# Goldilocks.net
KiCad netlist of a schematic drawn in EAGLE
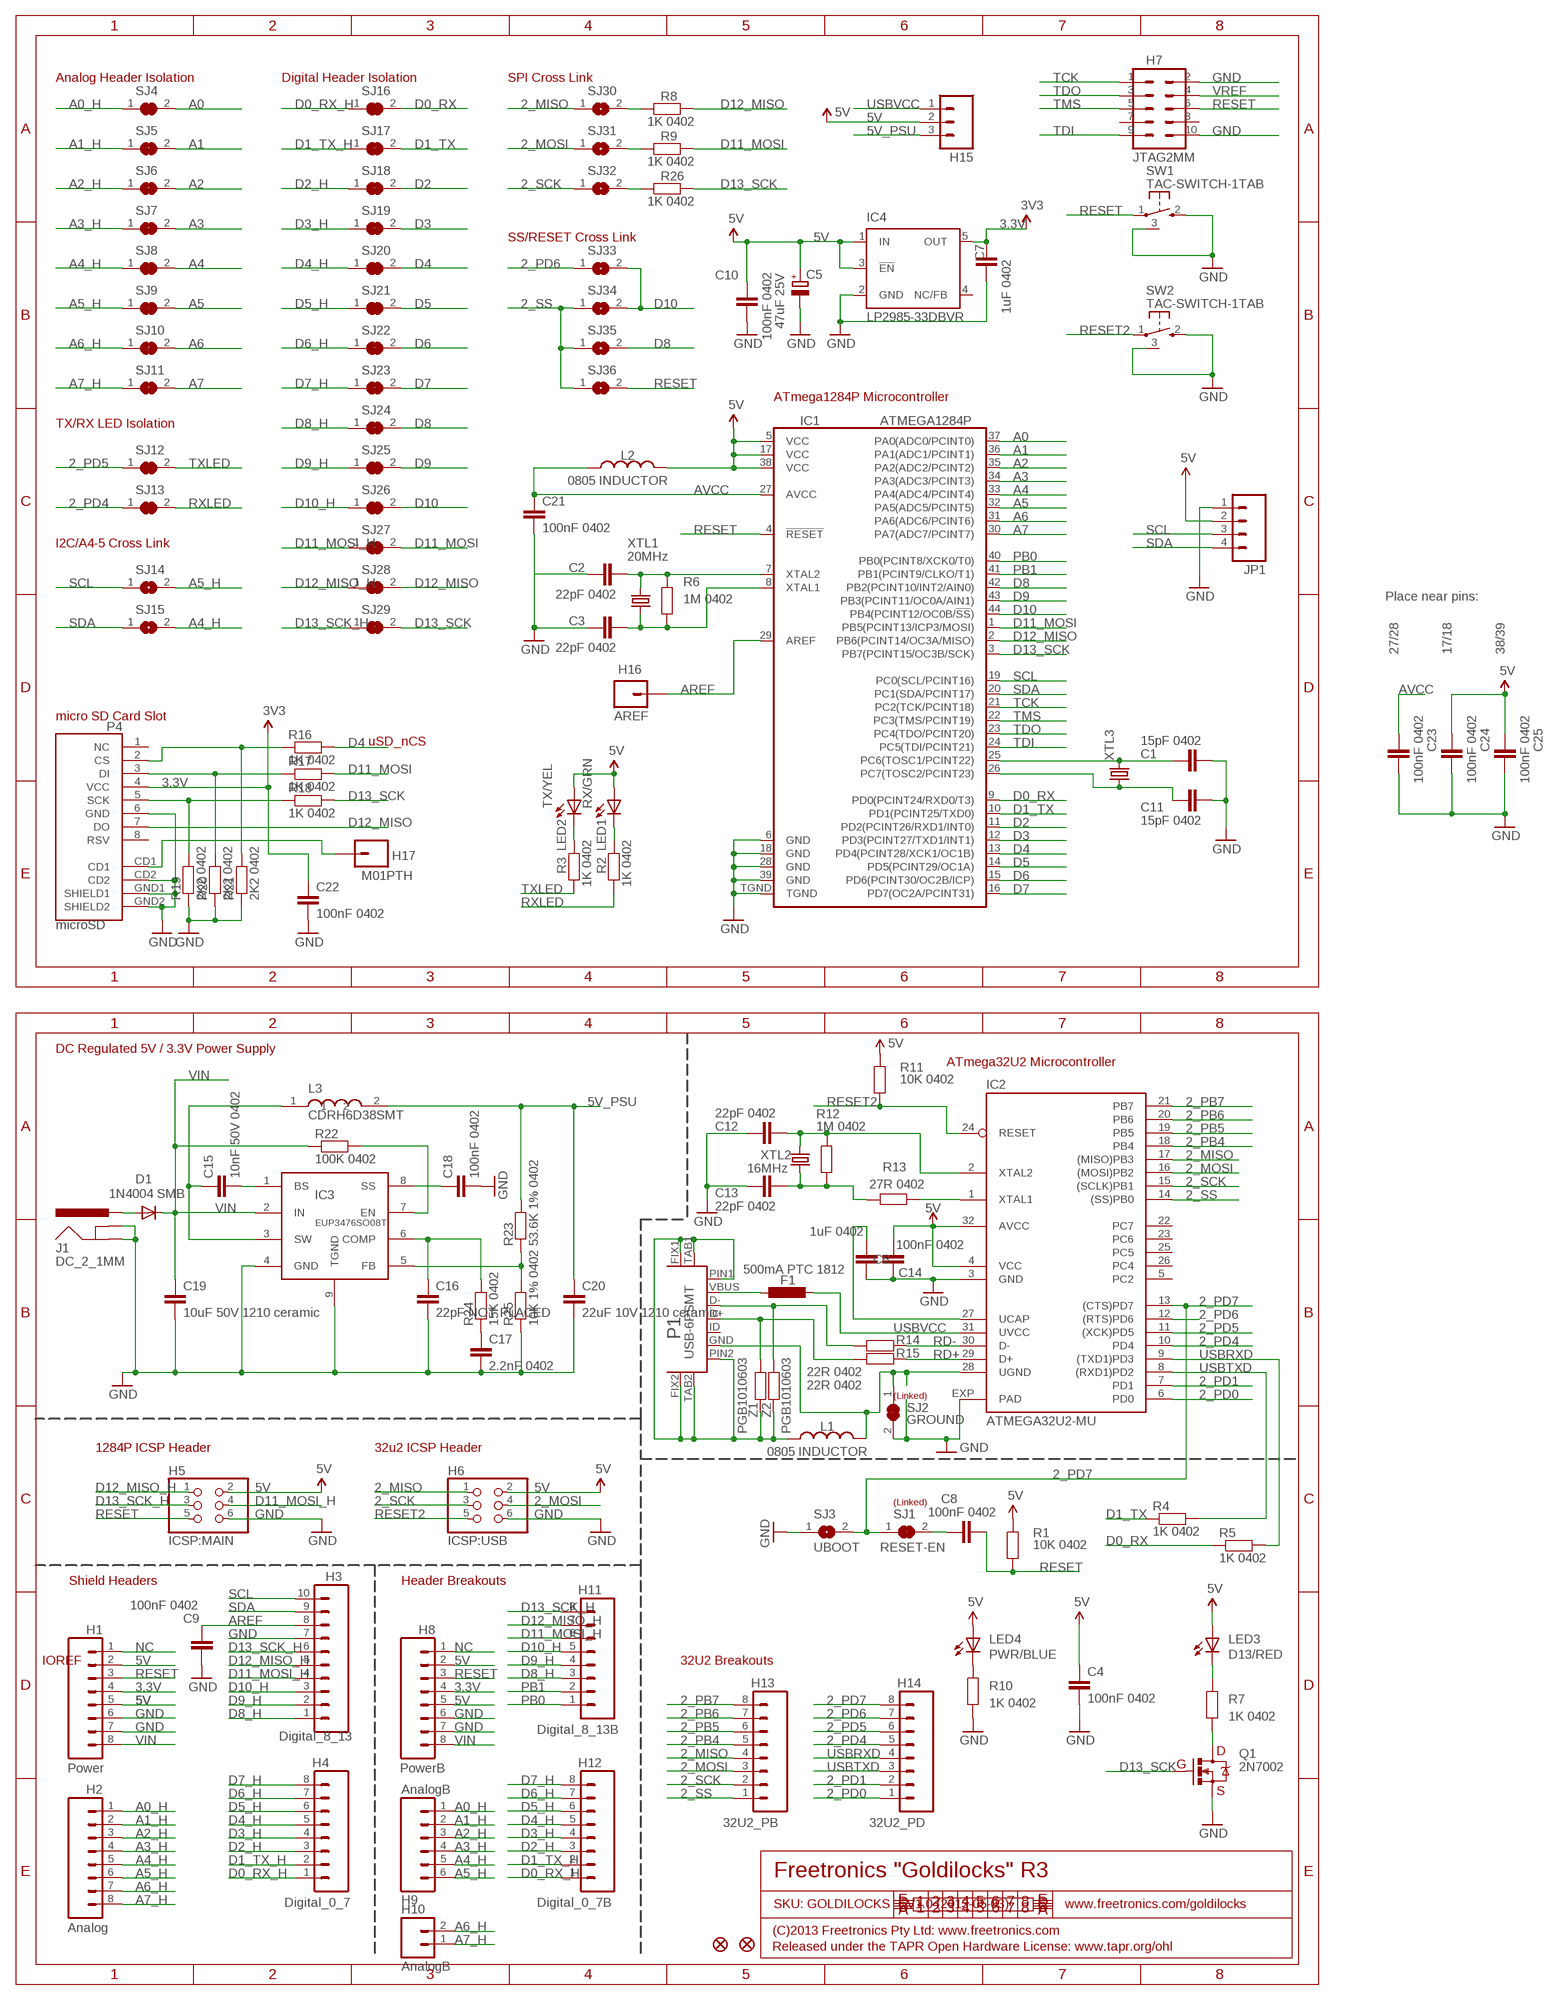
[diagram p0: schematic, sheet 1]

(export (version "E")
  (design (tool "Eeschema 10.0.6"))
  (components
    (comp (ref "C1")
      (value "15pF 0402")
      (footprint "eagle-import:0402C")
      (libsource (lib "eagle-import") (part "C-EU0402C"))
    )
    (comp (ref "C2")
      (value "22pF 0402")
      (footprint "eagle-import:0402C")
      (libsource (lib "eagle-import") (part "C-EU0402C"))
    )
    (comp (ref "C3")
      (value "22pF 0402")
      (footprint "eagle-import:0402C")
      (libsource (lib "eagle-import") (part "C-EU0402C"))
    )
    (comp (ref "C4")
      (value "100nF 0402")
      (footprint "eagle-import:0402C")
      (libsource (lib "eagle-import") (part "C-EU0402C"))
    )
    (comp (ref "C5")
      (value "47uF 25V")
      (footprint "eagle-import:PANASONIC_D")
      (libsource (lib "eagle-import") (part "CPOL-EUD"))
    )
    (comp (ref "C6")
      (value "1uF 0402")
      (footprint "eagle-import:0402C")
      (libsource (lib "eagle-import") (part "C-EU0402C"))
    )
    (comp (ref "C7")
      (value "1uF 0402")
      (footprint "eagle-import:0402C")
      (libsource (lib "eagle-import") (part "C-EU0402C"))
    )
    (comp (ref "C8")
      (value "100nF 0402")
      (footprint "eagle-import:0402C")
      (libsource (lib "eagle-import") (part "C-EU0402C"))
    )
    (comp (ref "C9")
      (value "100nF 0402")
      (footprint "eagle-import:0402C")
      (libsource (lib "eagle-import") (part "C-EU0402C"))
    )
    (comp (ref "C10")
      (value "100nF 0402")
      (footprint "eagle-import:0402C")
      (libsource (lib "eagle-import") (part "C-EU0402C"))
    )
    (comp (ref "C11")
      (value "15pF 0402")
      (footprint "eagle-import:0402C")
      (libsource (lib "eagle-import") (part "C-EU0402C"))
    )
    (comp (ref "C12")
      (value "22pF 0402")
      (footprint "eagle-import:0402C")
      (libsource (lib "eagle-import") (part "C-EU0402C"))
    )
    (comp (ref "C13")
      (value "22pF 0402")
      (footprint "eagle-import:0402C")
      (libsource (lib "eagle-import") (part "C-EU0402C"))
    )
    (comp (ref "C14")
      (value "100nF 0402")
      (footprint "eagle-import:0402C")
      (libsource (lib "eagle-import") (part "C-EU0402C"))
    )
    (comp (ref "C15")
      (value "10nF 50V 0402")
      (footprint "eagle-import:0402C")
      (libsource (lib "eagle-import") (part "C-EU0402C"))
    )
    (comp (ref "C16")
      (value "22pF NOT PLACED")
      (footprint "eagle-import:0402C")
      (libsource (lib "eagle-import") (part "C-EU0402C"))
    )
    (comp (ref "C17")
      (value "2.2nF 0402")
      (footprint "eagle-import:0402C")
      (libsource (lib "eagle-import") (part "C-EU0402C"))
    )
    (comp (ref "C18")
      (value "100nF 0402")
      (footprint "eagle-import:0402C")
      (libsource (lib "eagle-import") (part "C-EU0402C"))
    )
    (comp (ref "C19")
      (value "10uF 50V 1210 ceramic")
      (footprint "eagle-import:C1210")
      (libsource (lib "eagle-import") (part "C-EUC1210"))
    )
    (comp (ref "C20")
      (value "22uF 10V 1210 ceramic")
      (footprint "eagle-import:C1210")
      (libsource (lib "eagle-import") (part "C-EUC1210"))
    )
    (comp (ref "C21")
      (value "100nF 0402")
      (footprint "eagle-import:0402C")
      (libsource (lib "eagle-import") (part "C-EU0402C"))
    )
    (comp (ref "C22")
      (value "100nF 0402")
      (footprint "eagle-import:0402C")
      (libsource (lib "eagle-import") (part "C-EU0402C"))
    )
    (comp (ref "C23")
      (value "100nF 0402")
      (footprint "eagle-import:0402C")
      (libsource (lib "eagle-import") (part "C-EU0402C"))
    )
    (comp (ref "C24")
      (value "100nF 0402")
      (footprint "eagle-import:0402C")
      (libsource (lib "eagle-import") (part "C-EU0402C"))
    )
    (comp (ref "C25")
      (value "100nF 0402")
      (footprint "eagle-import:0402C")
      (libsource (lib "eagle-import") (part "C-EU0402C"))
    )
    (comp (ref "D1")
      (value "1N4004 SMB")
      (footprint "eagle-import:SMB-DIODE")
      (libsource (lib "eagle-import") (part "DIODESMB"))
    )
    (comp (ref "F1")
      (value "500mA PTC 1812")
      (footprint "eagle-import:L1812")
      (libsource (lib "eagle-import") (part "L-EUL1812"))
    )
    (comp (ref "H1")
      (value "Power")
      (footprint "eagle-import:1X08")
      (libsource (lib "eagle-import") (part "M08"))
    )
    (comp (ref "H2")
      (value "Analog")
      (footprint "eagle-import:1X08")
      (libsource (lib "eagle-import") (part "M08"))
    )
    (comp (ref "H3")
      (value "Digital_8_13")
      (footprint "eagle-import:1X10")
      (libsource (lib "eagle-import") (part "M100.1"))
    )
    (comp (ref "H4")
      (value "Digital_0_7")
      (footprint "eagle-import:1X08")
      (libsource (lib "eagle-import") (part "M08"))
    )
    (comp (ref "H5")
      (value "ICSP:MAIN")
      (footprint "eagle-import:2X03")
      (libsource (lib "eagle-import") (part "PINHD-2X3"))
    )
    (comp (ref "H6")
      (value "ICSP:USB")
      (footprint "eagle-import:2X03")
      (libsource (lib "eagle-import") (part "PINHD-2X3"))
    )
    (comp (ref "H7")
      (value "JTAG2MM")
      (footprint "eagle-import:SAMTEC-TMM-DOUBLE")
      (libsource (lib "eagle-import") (part "JTAG2MM"))
    )
    (comp (ref "H8")
      (value "PowerB")
      (footprint "eagle-import:1X08")
      (libsource (lib "eagle-import") (part "M08"))
    )
    (comp (ref "H9")
      (value "AnalogB")
      (footprint "eagle-import:1X06")
      (libsource (lib "eagle-import") (part "M06SIP"))
    )
    (comp (ref "H10")
      (value "AnalogB")
      (footprint "eagle-import:1X02")
      (libsource (lib "eagle-import") (part "M02PTH"))
    )
    (comp (ref "H11")
      (value "Digital_8_13B")
      (footprint "eagle-import:1X08")
      (libsource (lib "eagle-import") (part "M08"))
    )
    (comp (ref "H12")
      (value "Digital_0_7B")
      (footprint "eagle-import:1X08")
      (libsource (lib "eagle-import") (part "M08"))
    )
    (comp (ref "H13")
      (value "32U2_PB")
      (footprint "eagle-import:1X08")
      (libsource (lib "eagle-import") (part "M08"))
    )
    (comp (ref "H14")
      (value "32U2_PD")
      (footprint "eagle-import:1X08")
      (libsource (lib "eagle-import") (part "M08"))
    )
    (comp (ref "H15")
      (value "M03PTH")
      (footprint "eagle-import:1X03")
      (libsource (lib "eagle-import") (part "M03PTH"))
    )
    (comp (ref "H16")
      (value "AREF")
      (footprint "eagle-import:1X01")
      (libsource (lib "eagle-import") (part "M01PTH"))
    )
    (comp (ref "H17")
      (value "M01PTH")
      (footprint "eagle-import:1X01")
      (libsource (lib "eagle-import") (part "M01PTH"))
    )
    (comp (ref "IC1")
      (value "ATMEGA1284P")
      (footprint "eagle-import:QFN-44M1")
      (libsource (lib "eagle-import") (part "ATMEGA1284P"))
    )
    (comp (ref "IC2")
      (value "ATMEGA32U2-MU")
      (footprint "eagle-import:ATMEL_QFN32")
      (libsource (lib "eagle-import") (part "ATMEL_ATMEGA8U2-MUQFN"))
    )
    (comp (ref "IC3")
      (value "EUP3476SO08T")
      (footprint "eagle-import:SO08T")
      (libsource (lib "eagle-import") (part "EUP3476SO08T"))
    )
    (comp (ref "IC4")
      (value "LP2985-33DBVR")
      (footprint "eagle-import:TEXAS_SOT23-DBV")
      (libsource (lib "eagle-import") (part "TEXAS_TPS77033"))
    )
    (comp (ref "J1")
      (value "DC_2_1MM")
      (footprint "eagle-import:POWER_JACK_PTH")
      (libsource (lib "eagle-import") (part "POWER_JACKPTH"))
    )
    (comp (ref "JP1")
      (value "M04PTH")
      (footprint "eagle-import:1X04")
      (libsource (lib "eagle-import") (part "M04PTH"))
    )
    (comp (ref "L1")
      (value "0805 INDUCTOR")
      (footprint "eagle-import:0805-LARGE")
      (libsource (lib "eagle-import") (part "INDUCTOR0805-LARGE"))
    )
    (comp (ref "L2")
      (value "0805 INDUCTOR")
      (footprint "eagle-import:0805-LARGE")
      (libsource (lib "eagle-import") (part "INDUCTOR0805-LARGE"))
    )
    (comp (ref "L3")
      (value "CDRH6D38SMT")
      (footprint "eagle-import:CDRH")
      (libsource (lib "eagle-import") (part "CDRH6D38SMT"))
    )
    (comp (ref "LED1")
      (value "RX/GRN")
      (footprint "eagle-import:LED-0402")
      (libsource (lib "eagle-import") (part "LED0402"))
    )
    (comp (ref "LED2")
      (value "TX/YEL")
      (footprint "eagle-import:LED-0402")
      (libsource (lib "eagle-import") (part "LED0402"))
    )
    (comp (ref "LED3")
      (value "D13/RED")
      (footprint "eagle-import:LED-0402")
      (libsource (lib "eagle-import") (part "LED0402"))
    )
    (comp (ref "LED4")
      (value "PWR/BLUE")
      (footprint "eagle-import:LED-0402")
      (libsource (lib "eagle-import") (part "LED0402"))
    )
    (comp (ref "P1")
      (value "USB-6PSMT")
      (footprint "eagle-import:USB-MICROB-MB05PMXX")
      (libsource (lib "eagle-import") (part "USB-6PSMT"))
    )
    (comp (ref "P4")
      (value "microSD")
      (footprint "eagle-import:MICRO-SD-SOCKET-PP")
      (libsource (lib "eagle-import") (part "USD-SOCKETNEW"))
    )
    (comp (ref "Q1")
      (value "2N7002")
      (footprint "eagle-import:SOT23-3")
      (libsource (lib "eagle-import") (part "MOSFET-NCHANNELSMD"))
    )
    (comp (ref "R1")
      (value "10K 0402")
      (footprint "eagle-import:0402")
      (libsource (lib "eagle-import") (part "freetronics-jon_RESISTOR0402"))
    )
    (comp (ref "R2")
      (value "1K 0402")
      (footprint "eagle-import:0402")
      (libsource (lib "eagle-import") (part "freetronics-jon_RESISTOR0402"))
    )
    (comp (ref "R3")
      (value "1K 0402")
      (footprint "eagle-import:0402")
      (libsource (lib "eagle-import") (part "freetronics-jon_RESISTOR0402"))
    )
    (comp (ref "R4")
      (value "1K 0402")
      (footprint "eagle-import:0402")
      (libsource (lib "eagle-import") (part "freetronics-jon_RESISTOR0402"))
    )
    (comp (ref "R5")
      (value "1K 0402")
      (footprint "eagle-import:0402")
      (libsource (lib "eagle-import") (part "freetronics-jon_RESISTOR0402"))
    )
    (comp (ref "R6")
      (value "1M 0402")
      (footprint "eagle-import:0402")
      (libsource (lib "eagle-import") (part "freetronics-jon_RESISTOR0402"))
    )
    (comp (ref "R7")
      (value "1K 0402")
      (footprint "eagle-import:0402")
      (libsource (lib "eagle-import") (part "freetronics-jon_RESISTOR0402"))
    )
    (comp (ref "R8")
      (value "1K 0402")
      (footprint "eagle-import:0402")
      (libsource (lib "eagle-import") (part "freetronics-jon_RESISTOR0402"))
    )
    (comp (ref "R9")
      (value "1K 0402")
      (footprint "eagle-import:0402")
      (libsource (lib "eagle-import") (part "freetronics-jon_RESISTOR0402"))
    )
    (comp (ref "R10")
      (value "1K 0402")
      (footprint "eagle-import:0402")
      (libsource (lib "eagle-import") (part "freetronics-jon_RESISTOR0402"))
    )
    (comp (ref "R11")
      (value "10K 0402")
      (footprint "eagle-import:0402")
      (libsource (lib "eagle-import") (part "freetronics-jon_RESISTOR0402"))
    )
    (comp (ref "R12")
      (value "1M 0402")
      (footprint "eagle-import:0402")
      (libsource (lib "eagle-import") (part "freetronics-jon_RESISTOR0402"))
    )
    (comp (ref "R13")
      (value "27R 0402")
      (footprint "eagle-import:0402")
      (libsource (lib "eagle-import") (part "freetronics-jon_RESISTOR0402"))
    )
    (comp (ref "R14")
      (value "22R 0402")
      (footprint "eagle-import:0402")
      (libsource (lib "eagle-import") (part "freetronics-jon_RESISTOR0402"))
    )
    (comp (ref "R15")
      (value "22R 0402")
      (footprint "eagle-import:0402")
      (libsource (lib "eagle-import") (part "freetronics-jon_RESISTOR0402"))
    )
    (comp (ref "R16")
      (value "1K 0402")
      (footprint "eagle-import:0402")
      (libsource (lib "eagle-import") (part "freetronics-jon_RESISTOR0402"))
    )
    (comp (ref "R17")
      (value "1K 0402")
      (footprint "eagle-import:0402")
      (libsource (lib "eagle-import") (part "freetronics-jon_RESISTOR0402"))
    )
    (comp (ref "R18")
      (value "1K 0402")
      (footprint "eagle-import:0402")
      (libsource (lib "eagle-import") (part "freetronics-jon_RESISTOR0402"))
    )
    (comp (ref "R19")
      (value "2K2 0402")
      (footprint "eagle-import:0402")
      (libsource (lib "eagle-import") (part "freetronics-jon_RESISTOR0402"))
    )
    (comp (ref "R20")
      (value "2K2 0402")
      (footprint "eagle-import:0402")
      (libsource (lib "eagle-import") (part "freetronics-jon_RESISTOR0402"))
    )
    (comp (ref "R21")
      (value "2K2 0402")
      (footprint "eagle-import:0402")
      (libsource (lib "eagle-import") (part "freetronics-jon_RESISTOR0402"))
    )
    (comp (ref "R22")
      (value "100K 0402")
      (footprint "eagle-import:0402")
      (libsource (lib "eagle-import") (part "freetronics-jon_RESISTOR0402"))
    )
    (comp (ref "R23")
      (value "53.6K 1% 0402")
      (footprint "eagle-import:0402")
      (libsource (lib "eagle-import") (part "freetronics-jon_RESISTOR0402"))
    )
    (comp (ref "R24")
      (value "15K 0402")
      (footprint "eagle-import:0402")
      (libsource (lib "eagle-import") (part "freetronics-jon_RESISTOR0402"))
    )
    (comp (ref "R25")
      (value "10K 1% 0402")
      (footprint "eagle-import:0402")
      (libsource (lib "eagle-import") (part "freetronics-jon_RESISTOR0402"))
    )
    (comp (ref "R26")
      (value "1K 0402")
      (footprint "eagle-import:0402")
      (libsource (lib "eagle-import") (part "freetronics-jon_RESISTOR0402"))
    )
    (comp (ref "SJ1")
      (value "RESET-EN")
      (footprint "eagle-import:SJC")
      (libsource (lib "eagle-import") (part "SJCN"))
    )
    (comp (ref "SJ2")
      (value "GROUND")
      (footprint "eagle-import:SJC")
      (libsource (lib "eagle-import") (part "SJCN"))
    )
    (comp (ref "SJ3")
      (value "UBOOT")
      (footprint "eagle-import:SJ")
      (libsource (lib "eagle-import") (part "jumper_SJ"))
    )
    (comp (ref "SJ4")
      (value "SJC0402")
      (footprint "eagle-import:0402SJC")
      (libsource (lib "eagle-import") (part "SJC0402"))
    )
    (comp (ref "SJ5")
      (value "SJC0402")
      (footprint "eagle-import:0402SJC")
      (libsource (lib "eagle-import") (part "SJC0402"))
    )
    (comp (ref "SJ6")
      (value "SJC0402")
      (footprint "eagle-import:0402SJC")
      (libsource (lib "eagle-import") (part "SJC0402"))
    )
    (comp (ref "SJ7")
      (value "SJC0402")
      (footprint "eagle-import:0402SJC")
      (libsource (lib "eagle-import") (part "SJC0402"))
    )
    (comp (ref "SJ8")
      (value "SJC0402")
      (footprint "eagle-import:0402SJC")
      (libsource (lib "eagle-import") (part "SJC0402"))
    )
    (comp (ref "SJ9")
      (value "SJC0402")
      (footprint "eagle-import:0402SJC")
      (libsource (lib "eagle-import") (part "SJC0402"))
    )
    (comp (ref "SJ10")
      (value "SJC0402")
      (footprint "eagle-import:0402SJC")
      (libsource (lib "eagle-import") (part "SJC0402"))
    )
    (comp (ref "SJ11")
      (value "SJC0402")
      (footprint "eagle-import:0402SJC")
      (libsource (lib "eagle-import") (part "SJC0402"))
    )
    (comp (ref "SJ12")
      (value "SJC0402")
      (footprint "eagle-import:0402SJC")
      (libsource (lib "eagle-import") (part "SJC0402"))
    )
    (comp (ref "SJ13")
      (value "SJC0402")
      (footprint "eagle-import:0402SJC")
      (libsource (lib "eagle-import") (part "SJC0402"))
    )
    (comp (ref "SJ14")
      (value "SJ")
      (footprint "eagle-import:SJ")
      (libsource (lib "eagle-import") (part "SJ"))
    )
    (comp (ref "SJ15")
      (value "SJ")
      (footprint "eagle-import:SJ")
      (libsource (lib "eagle-import") (part "SJ"))
    )
    (comp (ref "SJ16")
      (value "SJC0402")
      (footprint "eagle-import:0402SJC")
      (libsource (lib "eagle-import") (part "SJC0402"))
    )
    (comp (ref "SJ17")
      (value "SJC0402")
      (footprint "eagle-import:0402SJC")
      (libsource (lib "eagle-import") (part "SJC0402"))
    )
    (comp (ref "SJ18")
      (value "SJC0402")
      (footprint "eagle-import:0402SJC")
      (libsource (lib "eagle-import") (part "SJC0402"))
    )
    (comp (ref "SJ19")
      (value "SJC0402")
      (footprint "eagle-import:0402SJC")
      (libsource (lib "eagle-import") (part "SJC0402"))
    )
    (comp (ref "SJ20")
      (value "SJC0402")
      (footprint "eagle-import:0402SJC")
      (libsource (lib "eagle-import") (part "SJC0402"))
    )
    (comp (ref "SJ21")
      (value "SJC0402")
      (footprint "eagle-import:0402SJC")
      (libsource (lib "eagle-import") (part "SJC0402"))
    )
    (comp (ref "SJ22")
      (value "SJC0402")
      (footprint "eagle-import:0402SJC")
      (libsource (lib "eagle-import") (part "SJC0402"))
    )
    (comp (ref "SJ23")
      (value "SJC0402")
      (footprint "eagle-import:0402SJC")
      (libsource (lib "eagle-import") (part "SJC0402"))
    )
    (comp (ref "SJ24")
      (value "SJC0402")
      (footprint "eagle-import:0402SJC")
      (libsource (lib "eagle-import") (part "SJC0402"))
    )
    (comp (ref "SJ25")
      (value "SJC0402")
      (footprint "eagle-import:0402SJC")
      (libsource (lib "eagle-import") (part "SJC0402"))
    )
    (comp (ref "SJ26")
      (value "SJC0402")
      (footprint "eagle-import:0402SJC")
      (libsource (lib "eagle-import") (part "SJC0402"))
    )
    (comp (ref "SJ27")
      (value "SJC0402")
      (footprint "eagle-import:0402SJC")
      (libsource (lib "eagle-import") (part "SJC0402"))
    )
    (comp (ref "SJ28")
      (value "SJC0402")
      (footprint "eagle-import:0402SJC")
      (libsource (lib "eagle-import") (part "SJC0402"))
    )
    (comp (ref "SJ29")
      (value "SJC0402")
      (footprint "eagle-import:0402SJC")
      (libsource (lib "eagle-import") (part "SJC0402"))
    )
    (comp (ref "SJ30")
      (value "MISO")
      (footprint "eagle-import:SJ")
      (libsource (lib "eagle-import") (part "SJN"))
    )
    (comp (ref "SJ31")
      (value "MOSI")
      (footprint "eagle-import:SJ")
      (libsource (lib "eagle-import") (part "SJN"))
    )
    (comp (ref "SJ32")
      (value "SCK")
      (footprint "eagle-import:SJ")
      (libsource (lib "eagle-import") (part "SJN"))
    )
    (comp (ref "SJ33")
      (value "SJN")
      (footprint "eagle-import:SJ")
      (libsource (lib "eagle-import") (part "SJN"))
    )
    (comp (ref "SJ34")
      (value "SJN")
      (footprint "eagle-import:SJ")
      (libsource (lib "eagle-import") (part "SJN"))
    )
    (comp (ref "SJ35")
      (value "SJN")
      (footprint "eagle-import:SJ")
      (libsource (lib "eagle-import") (part "SJN"))
    )
    (comp (ref "SJ36")
      (value "SJN")
      (footprint "eagle-import:SJ")
      (libsource (lib "eagle-import") (part "SJN"))
    )
    (comp (ref "SW1")
      (value "TAC-SWITCH-1TAB")
      (footprint "eagle-import:TACT-VERT-1TAB")
      (libsource (lib "eagle-import") (part "TAC-SWITCH-1TAB"))
    )
    (comp (ref "SW2")
      (value "TAC-SWITCH-1TAB")
      (footprint "eagle-import:TACT-VERT-1TAB")
      (libsource (lib "eagle-import") (part "TAC-SWITCH-1TAB"))
    )
    (comp (ref "U$5")
      (value "FIDUCIAL1X2.5")
      (footprint "eagle-import:FIDUCIAL-1X2.5")
      (libsource (lib "eagle-import") (part "FIDUCIAL1X2.5"))
    )
    (comp (ref "U$14")
      (value "FIDUCIAL1X2.5")
      (footprint "eagle-import:FIDUCIAL-1X2.5")
      (libsource (lib "eagle-import") (part "FIDUCIAL1X2.5"))
    )
    (comp (ref "XTL1")
      (value "20MHz")
      (footprint "eagle-import:HC49U-V")
      (libsource (lib "eagle-import") (part "CRYSTALHC49UV"))
    )
    (comp (ref "XTL2")
      (value "16MHz")
      (footprint "eagle-import:HC49U-V")
      (libsource (lib "eagle-import") (part "CRYSTALHC49UV"))
    )
    (comp (ref "XTL3")
      (value "CRYSTALTC38H")
      (footprint "eagle-import:TC38H")
      (libsource (lib "eagle-import") (part "freetronics-original_CRYSTALTC38H"))
    )
    (comp (ref "Z1")
      (value "PGB1010603")
      (footprint "eagle-import:0603")
      (libsource (lib "eagle-import") (part "RESISTOR0603"))
    )
    (comp (ref "Z2")
      (value "PGB1010603")
      (footprint "eagle-import:0603")
      (libsource (lib "eagle-import") (part "RESISTOR0603"))
    )
  )
  (nets
    (net (code "1") (name "/2_MISO") (class "Default")
      (node (ref "H13") (pin "4") (pinfunction "4_4") (pintype "passive"))
      (node (ref "H6") (pin "1") (pinfunction "1_1") (pintype "passive"))
      (node (ref "IC2") (pin "17") (pinfunction "(MISO)PB3_17") (pintype "bidirectional"))
      (node (ref "SJ30") (pin "1") (pinfunction "1_1") (pintype "passive"))
    )
    (net (code "2") (name "/2_MOSI") (class "Default")
      (node (ref "H13") (pin "3") (pinfunction "3_3") (pintype "passive"))
      (node (ref "H6") (pin "4") (pinfunction "4_4") (pintype "passive"))
      (node (ref "IC2") (pin "16") (pinfunction "(MOSI)PB2_16") (pintype "bidirectional"))
      (node (ref "SJ31") (pin "1") (pinfunction "1_1") (pintype "passive"))
    )
    (net (code "3") (name "/2_PB4") (class "Default")
      (node (ref "H13") (pin "5") (pinfunction "5_5") (pintype "passive"))
      (node (ref "IC2") (pin "18") (pinfunction "PB4_18") (pintype "bidirectional"))
    )
    (net (code "4") (name "/2_PB5") (class "Default")
      (node (ref "H13") (pin "6") (pinfunction "6_6") (pintype "passive"))
      (node (ref "IC2") (pin "19") (pinfunction "PB5_19") (pintype "bidirectional"))
    )
    (net (code "5") (name "/2_PB6") (class "Default")
      (node (ref "H13") (pin "7") (pinfunction "7_7") (pintype "passive"))
      (node (ref "IC2") (pin "20") (pinfunction "PB6_20") (pintype "bidirectional"))
    )
    (net (code "6") (name "/2_PB7") (class "Default")
      (node (ref "H13") (pin "8") (pinfunction "8_8") (pintype "passive"))
      (node (ref "IC2") (pin "21") (pinfunction "PB7_21") (pintype "bidirectional"))
    )
    (net (code "7") (name "/2_PD0") (class "Default")
      (node (ref "H14") (pin "1") (pinfunction "1_1") (pintype "passive"))
      (node (ref "IC2") (pin "6") (pinfunction "PD0_6") (pintype "bidirectional"))
    )
    (net (code "8") (name "/2_PD1") (class "Default")
      (node (ref "H14") (pin "2") (pinfunction "2_2") (pintype "passive"))
      (node (ref "IC2") (pin "7") (pinfunction "PD1_7") (pintype "bidirectional"))
    )
    (net (code "9") (name "/2_PD4") (class "Default")
      (node (ref "H14") (pin "5") (pinfunction "5_5") (pintype "passive"))
      (node (ref "IC2") (pin "10") (pinfunction "PD4_10") (pintype "bidirectional"))
      (node (ref "SJ13") (pin "1") (pinfunction "1_1") (pintype "passive"))
    )
    (net (code "10") (name "/2_PD5") (class "Default")
      (node (ref "H14") (pin "6") (pinfunction "6_6") (pintype "passive"))
      (node (ref "IC2") (pin "11") (pinfunction "(XCK)PD5_11") (pintype "bidirectional"))
      (node (ref "SJ12") (pin "1") (pinfunction "1_1") (pintype "passive"))
    )
    (net (code "11") (name "/2_PD6") (class "Default")
      (node (ref "H14") (pin "7") (pinfunction "7_7") (pintype "passive"))
      (node (ref "IC2") (pin "12") (pinfunction "(RTS)PD6_12") (pintype "bidirectional"))
      (node (ref "SJ33") (pin "1") (pinfunction "1_1") (pintype "passive"))
    )
    (net (code "12") (name "/2_PD7") (class "Default")
      (node (ref "H14") (pin "8") (pinfunction "8_8") (pintype "passive"))
      (node (ref "IC2") (pin "13") (pinfunction "(CTS)PD7_13") (pintype "bidirectional"))
      (node (ref "SJ1") (pin "1") (pinfunction "1_1") (pintype "passive"))
      (node (ref "SJ3") (pin "2") (pinfunction "2_2") (pintype "passive"))
    )
    (net (code "13") (name "/2_SCK") (class "Default")
      (node (ref "H13") (pin "2") (pinfunction "2_2") (pintype "passive"))
      (node (ref "H6") (pin "3") (pinfunction "3_3") (pintype "passive"))
      (node (ref "IC2") (pin "15") (pinfunction "(SCLK)PB1_15") (pintype "bidirectional"))
      (node (ref "SJ32") (pin "1") (pinfunction "1_1") (pintype "passive"))
    )
    (net (code "14") (name "/2_SS") (class "Default")
      (node (ref "H13") (pin "1") (pinfunction "1_1") (pintype "passive"))
      (node (ref "IC2") (pin "14") (pinfunction "(SS)PB0_14") (pintype "bidirectional"))
      (node (ref "SJ34") (pin "1") (pinfunction "1_1") (pintype "passive"))
      (node (ref "SJ35") (pin "1") (pinfunction "1_1") (pintype "passive"))
      (node (ref "SJ36") (pin "1") (pinfunction "1_1") (pintype "passive"))
    )
    (net (code "15") (name "/5V_PSU") (class "Default")
      (node (ref "C20") (pin "1") (pinfunction "1_1") (pintype "passive"))
      (node (ref "H15") (pin "3") (pinfunction "3_3") (pintype "passive"))
      (node (ref "L3") (pin "2") (pinfunction "2_2") (pintype "bidirectional"))
      (node (ref "R23") (pin "2") (pinfunction "2_2") (pintype "passive"))
    )
    (net (code "16") (name "/A0") (class "Default")
      (node (ref "IC1") (pin "37") (pinfunction "PA0(ADC0/PCINT0)_37") (pintype "bidirectional"))
      (node (ref "SJ4") (pin "2") (pinfunction "2_2") (pintype "passive"))
    )
    (net (code "17") (name "/A0_H") (class "Default")
      (node (ref "H2") (pin "1") (pinfunction "1_1") (pintype "passive"))
      (node (ref "H9") (pin "1") (pinfunction "1_1") (pintype "passive"))
      (node (ref "SJ4") (pin "1") (pinfunction "1_1") (pintype "passive"))
    )
    (net (code "18") (name "/A1") (class "Default")
      (node (ref "IC1") (pin "36") (pinfunction "PA1(ADC1/PCINT1)_36") (pintype "bidirectional"))
      (node (ref "SJ5") (pin "2") (pinfunction "2_2") (pintype "passive"))
    )
    (net (code "19") (name "/A1_H") (class "Default")
      (node (ref "H2") (pin "2") (pinfunction "2_2") (pintype "passive"))
      (node (ref "H9") (pin "2") (pinfunction "2_2") (pintype "passive"))
      (node (ref "SJ5") (pin "1") (pinfunction "1_1") (pintype "passive"))
    )
    (net (code "20") (name "/A2") (class "Default")
      (node (ref "IC1") (pin "35") (pinfunction "PA2(ADC2/PCINT2)_35") (pintype "bidirectional"))
      (node (ref "SJ6") (pin "2") (pinfunction "2_2") (pintype "passive"))
    )
    (net (code "21") (name "/A2_H") (class "Default")
      (node (ref "H2") (pin "3") (pinfunction "3_3") (pintype "passive"))
      (node (ref "H9") (pin "3") (pinfunction "3_3") (pintype "passive"))
      (node (ref "SJ6") (pin "1") (pinfunction "1_1") (pintype "passive"))
    )
    (net (code "22") (name "/A3") (class "Default")
      (node (ref "IC1") (pin "34") (pinfunction "PA3(ADC3/PCINT3)_34") (pintype "bidirectional"))
      (node (ref "SJ7") (pin "2") (pinfunction "2_2") (pintype "passive"))
    )
    (net (code "23") (name "/A3_H") (class "Default")
      (node (ref "H2") (pin "4") (pinfunction "4_4") (pintype "passive"))
      (node (ref "H9") (pin "4") (pinfunction "4_4") (pintype "passive"))
      (node (ref "SJ7") (pin "1") (pinfunction "1_1") (pintype "passive"))
    )
    (net (code "24") (name "/A4") (class "Default")
      (node (ref "IC1") (pin "33") (pinfunction "PA4(ADC4/PCINT4)_33") (pintype "bidirectional"))
      (node (ref "SJ8") (pin "2") (pinfunction "2_2") (pintype "passive"))
    )
    (net (code "25") (name "/A4_H") (class "Default")
      (node (ref "H2") (pin "5") (pinfunction "5_5") (pintype "passive"))
      (node (ref "H9") (pin "5") (pinfunction "5_5") (pintype "passive"))
      (node (ref "SJ15") (pin "2") (pinfunction "2_2") (pintype "passive"))
      (node (ref "SJ8") (pin "1") (pinfunction "1_1") (pintype "passive"))
    )
    (net (code "26") (name "/A5") (class "Default")
      (node (ref "IC1") (pin "32") (pinfunction "PA5(ADC5/PCINT5)_32") (pintype "bidirectional"))
      (node (ref "SJ9") (pin "2") (pinfunction "2_2") (pintype "passive"))
    )
    (net (code "27") (name "/A5_H") (class "Default")
      (node (ref "H2") (pin "6") (pinfunction "6_6") (pintype "passive"))
      (node (ref "H9") (pin "6") (pinfunction "6_6") (pintype "passive"))
      (node (ref "SJ14") (pin "2") (pinfunction "2_2") (pintype "passive"))
      (node (ref "SJ9") (pin "1") (pinfunction "1_1") (pintype "passive"))
    )
    (net (code "28") (name "/A6") (class "Default")
      (node (ref "IC1") (pin "31") (pinfunction "PA6(ADC6/PCINT6)_31") (pintype "bidirectional"))
      (node (ref "SJ10") (pin "2") (pinfunction "2_2") (pintype "passive"))
    )
    (net (code "29") (name "/A6_H") (class "Default")
      (node (ref "H10") (pin "2") (pinfunction "2_2") (pintype "passive"))
      (node (ref "H2") (pin "7") (pinfunction "7_7") (pintype "passive"))
      (node (ref "SJ10") (pin "1") (pinfunction "1_1") (pintype "passive"))
    )
    (net (code "30") (name "/A7") (class "Default")
      (node (ref "IC1") (pin "30") (pinfunction "PA7(ADC7/PCINT7)_30") (pintype "bidirectional"))
      (node (ref "SJ11") (pin "2") (pinfunction "2_2") (pintype "passive"))
    )
    (net (code "31") (name "/A7_H") (class "Default")
      (node (ref "H10") (pin "1") (pinfunction "1_1") (pintype "passive"))
      (node (ref "H2") (pin "8") (pinfunction "8_8") (pintype "passive"))
      (node (ref "SJ11") (pin "1") (pinfunction "1_1") (pintype "passive"))
    )
    (net (code "32") (name "/AREF") (class "Default")
      (node (ref "C9") (pin "1") (pinfunction "1_1") (pintype "passive"))
      (node (ref "H16") (pin "1") (pinfunction "1_1") (pintype "passive"))
      (node (ref "H3") (pin "8") (pinfunction "8_8") (pintype "passive"))
      (node (ref "IC1") (pin "29") (pinfunction "AREF_29") (pintype "bidirectional"))
    )
    (net (code "33") (name "/AVCC") (class "Default")
      (node (ref "C21") (pin "1") (pinfunction "1_1") (pintype "passive"))
      (node (ref "C23") (pin "1") (pinfunction "1_1") (pintype "passive"))
      (node (ref "IC1") (pin "27") (pinfunction "AVCC_27") (pintype "bidirectional"))
      (node (ref "L2") (pin "1") (pinfunction "1_1") (pintype "passive"))
    )
    (net (code "34") (name "/D0_RX") (class "Default")
      (node (ref "IC1") (pin "9") (pinfunction "PD0(PCINT24/RXD0/T3)_9") (pintype "bidirectional"))
      (node (ref "R5") (pin "1") (pinfunction "1_1") (pintype "passive"))
      (node (ref "SJ16") (pin "2") (pinfunction "2_2") (pintype "passive"))
    )
    (net (code "35") (name "/D0_RX_H") (class "Default")
      (node (ref "H12") (pin "1") (pinfunction "1_1") (pintype "passive"))
      (node (ref "H4") (pin "1") (pinfunction "1_1") (pintype "passive"))
      (node (ref "SJ16") (pin "1") (pinfunction "1_1") (pintype "passive"))
    )
    (net (code "36") (name "/D1_TX") (class "Default")
      (node (ref "IC1") (pin "10") (pinfunction "PD1(PCINT25/TXD0)_10") (pintype "bidirectional"))
      (node (ref "R4") (pin "1") (pinfunction "1_1") (pintype "passive"))
      (node (ref "SJ17") (pin "2") (pinfunction "2_2") (pintype "passive"))
    )
    (net (code "37") (name "/D1_TX_H") (class "Default")
      (node (ref "H12") (pin "2") (pinfunction "2_2") (pintype "passive"))
      (node (ref "H4") (pin "2") (pinfunction "2_2") (pintype "passive"))
      (node (ref "SJ17") (pin "1") (pinfunction "1_1") (pintype "passive"))
    )
    (net (code "38") (name "/D2") (class "Default")
      (node (ref "IC1") (pin "11") (pinfunction "PD2(PCINT26/RXD1/INT0)_11") (pintype "bidirectional"))
      (node (ref "SJ18") (pin "2") (pinfunction "2_2") (pintype "passive"))
    )
    (net (code "39") (name "/D2_H") (class "Default")
      (node (ref "H12") (pin "3") (pinfunction "3_3") (pintype "passive"))
      (node (ref "H4") (pin "3") (pinfunction "3_3") (pintype "passive"))
      (node (ref "SJ18") (pin "1") (pinfunction "1_1") (pintype "passive"))
    )
    (net (code "40") (name "/D3") (class "Default")
      (node (ref "IC1") (pin "12") (pinfunction "PD3(PCINT27/TXD1/INT1)_12") (pintype "bidirectional"))
      (node (ref "SJ19") (pin "2") (pinfunction "2_2") (pintype "passive"))
    )
    (net (code "41") (name "/D3_H") (class "Default")
      (node (ref "H12") (pin "4") (pinfunction "4_4") (pintype "passive"))
      (node (ref "H4") (pin "4") (pinfunction "4_4") (pintype "passive"))
      (node (ref "SJ19") (pin "1") (pinfunction "1_1") (pintype "passive"))
    )
    (net (code "42") (name "/D4") (class "Default")
      (node (ref "IC1") (pin "13") (pinfunction "PD4(PCINT28/XCK1/OC1B)_13") (pintype "bidirectional"))
      (node (ref "R16") (pin "2") (pinfunction "2_2") (pintype "passive"))
      (node (ref "SJ20") (pin "2") (pinfunction "2_2") (pintype "passive"))
    )
    (net (code "43") (name "/D4_H") (class "Default")
      (node (ref "H12") (pin "5") (pinfunction "5_5") (pintype "passive"))
      (node (ref "H4") (pin "5") (pinfunction "5_5") (pintype "passive"))
      (node (ref "SJ20") (pin "1") (pinfunction "1_1") (pintype "passive"))
    )
    (net (code "44") (name "/D5") (class "Default")
      (node (ref "IC1") (pin "14") (pinfunction "PD5(PCINT29/OC1A)_14") (pintype "bidirectional"))
      (node (ref "SJ21") (pin "2") (pinfunction "2_2") (pintype "passive"))
    )
    (net (code "45") (name "/D5_H") (class "Default")
      (node (ref "H12") (pin "6") (pinfunction "6_6") (pintype "passive"))
      (node (ref "H4") (pin "6") (pinfunction "6_6") (pintype "passive"))
      (node (ref "SJ21") (pin "1") (pinfunction "1_1") (pintype "passive"))
    )
    (net (code "46") (name "/D6") (class "Default")
      (node (ref "IC1") (pin "15") (pinfunction "PD6(PCINT30/OC2B/ICP)_15") (pintype "bidirectional"))
      (node (ref "SJ22") (pin "2") (pinfunction "2_2") (pintype "passive"))
    )
    (net (code "47") (name "/D6_H") (class "Default")
      (node (ref "H12") (pin "7") (pinfunction "7_7") (pintype "passive"))
      (node (ref "H4") (pin "7") (pinfunction "7_7") (pintype "passive"))
      (node (ref "SJ22") (pin "1") (pinfunction "1_1") (pintype "passive"))
    )
    (net (code "48") (name "/D7") (class "Default")
      (node (ref "IC1") (pin "16") (pinfunction "PD7(OC2A/PCINT31)_16") (pintype "bidirectional"))
      (node (ref "SJ23") (pin "2") (pinfunction "2_2") (pintype "passive"))
    )
    (net (code "49") (name "/D7_H") (class "Default")
      (node (ref "H12") (pin "8") (pinfunction "8_8") (pintype "passive"))
      (node (ref "H4") (pin "8") (pinfunction "8_8") (pintype "passive"))
      (node (ref "SJ23") (pin "1") (pinfunction "1_1") (pintype "passive"))
    )
    (net (code "50") (name "/D8") (class "Default")
      (node (ref "IC1") (pin "42") (pinfunction "PB2(PCINT10/INT2/AIN0)_42") (pintype "bidirectional"))
      (node (ref "SJ24") (pin "2") (pinfunction "2_2") (pintype "passive"))
      (node (ref "SJ35") (pin "2") (pinfunction "2_2") (pintype "passive"))
    )
    (net (code "51") (name "/D8_H") (class "Default")
      (node (ref "H11") (pin "3") (pinfunction "3_3") (pintype "passive"))
      (node (ref "H3") (pin "1") (pinfunction "1_1") (pintype "passive"))
      (node (ref "SJ24") (pin "1") (pinfunction "1_1") (pintype "passive"))
    )
    (net (code "52") (name "/D9") (class "Default")
      (node (ref "IC1") (pin "43") (pinfunction "PB3(PCINT11/OC0A/AIN1)_43") (pintype "bidirectional"))
      (node (ref "SJ25") (pin "2") (pinfunction "2_2") (pintype "passive"))
    )
    (net (code "53") (name "/D9_H") (class "Default")
      (node (ref "H11") (pin "4") (pinfunction "4_4") (pintype "passive"))
      (node (ref "H3") (pin "2") (pinfunction "2_2") (pintype "passive"))
      (node (ref "SJ25") (pin "1") (pinfunction "1_1") (pintype "passive"))
    )
    (net (code "54") (name "/D10") (class "Default")
      (node (ref "IC1") (pin "44") (pinfunction "PB4(PCINT12/OC0B/~{SS})_44") (pintype "bidirectional"))
      (node (ref "SJ26") (pin "2") (pinfunction "2_2") (pintype "passive"))
      (node (ref "SJ33") (pin "2") (pinfunction "2_2") (pintype "passive"))
      (node (ref "SJ34") (pin "2") (pinfunction "2_2") (pintype "passive"))
    )
    (net (code "55") (name "/D10_H") (class "Default")
      (node (ref "H11") (pin "5") (pinfunction "5_5") (pintype "passive"))
      (node (ref "H3") (pin "3") (pinfunction "3_3") (pintype "passive"))
      (node (ref "SJ26") (pin "1") (pinfunction "1_1") (pintype "passive"))
    )
    (net (code "56") (name "/D11_MOSI") (class "Default")
      (node (ref "H5") (pin "4") (pinfunction "4_4") (pintype "passive"))
      (node (ref "IC1") (pin "1") (pinfunction "PB5(PCINT13/ICP3/MOSI)_1") (pintype "bidirectional"))
      (node (ref "R17") (pin "2") (pinfunction "2_2") (pintype "passive"))
      (node (ref "R9") (pin "2") (pinfunction "2_2") (pintype "passive"))
      (node (ref "SJ27") (pin "2") (pinfunction "2_2") (pintype "passive"))
    )
    (net (code "57") (name "/D11_MOSI_H") (class "Default")
      (node (ref "H11") (pin "6") (pinfunction "6_6") (pintype "passive"))
      (node (ref "H3") (pin "4") (pinfunction "4_4") (pintype "passive"))
      (node (ref "SJ27") (pin "1") (pinfunction "1_1") (pintype "passive"))
    )
    (net (code "58") (name "/D12_MISO") (class "Default")
      (node (ref "H5") (pin "1") (pinfunction "1_1") (pintype "passive"))
      (node (ref "IC1") (pin "2") (pinfunction "PB6(PCINT14/OC3A/MISO)_2") (pintype "bidirectional"))
      (node (ref "P4") (pin "7") (pinfunction "DO_7") (pintype "bidirectional"))
      (node (ref "R8") (pin "2") (pinfunction "2_2") (pintype "passive"))
      (node (ref "SJ28") (pin "2") (pinfunction "2_2") (pintype "passive"))
    )
    (net (code "59") (name "/D12_MISO_H") (class "Default")
      (node (ref "H11") (pin "7") (pinfunction "7_7") (pintype "passive"))
      (node (ref "H3") (pin "5") (pinfunction "5_5") (pintype "passive"))
      (node (ref "SJ28") (pin "1") (pinfunction "1_1") (pintype "passive"))
    )
    (net (code "60") (name "/D13_SCK") (class "Default")
      (node (ref "H5") (pin "3") (pinfunction "3_3") (pintype "passive"))
      (node (ref "IC1") (pin "3") (pinfunction "PB7(PCINT15/OC3B/SCK)_3") (pintype "bidirectional"))
      (node (ref "Q1") (pin "1") (pinfunction "G_1") (pintype "passive"))
      (node (ref "R18") (pin "2") (pinfunction "2_2") (pintype "passive"))
      (node (ref "R26") (pin "2") (pinfunction "2_2") (pintype "passive"))
      (node (ref "SJ29") (pin "2") (pinfunction "2_2") (pintype "passive"))
    )
    (net (code "61") (name "/D13_SCK_H") (class "Default")
      (node (ref "H11") (pin "8") (pinfunction "8_8") (pintype "passive"))
      (node (ref "H3") (pin "6") (pinfunction "6_6") (pintype "passive"))
      (node (ref "SJ29") (pin "1") (pinfunction "1_1") (pintype "passive"))
    )
    (net (code "62") (name "/NC") (class "Default")
      (node (ref "H1") (pin "1") (pinfunction "1_1") (pintype "passive"))
      (node (ref "H8") (pin "1") (pinfunction "1_1") (pintype "passive"))
    )
    (net (code "63") (name "/PB0") (class "Default")
      (node (ref "H11") (pin "1") (pinfunction "1_1") (pintype "passive"))
      (node (ref "IC1") (pin "40") (pinfunction "PB0(PCINT8/XCK0/T0)_40") (pintype "bidirectional"))
    )
    (net (code "64") (name "/PB1") (class "Default")
      (node (ref "H11") (pin "2") (pinfunction "2_2") (pintype "passive"))
      (node (ref "IC1") (pin "41") (pinfunction "PB1(PCINT9/CLKO/T1)_41") (pintype "bidirectional"))
    )
    (net (code "65") (name "/RD+") (class "Default")
      (node (ref "IC2") (pin "29") (pinfunction "D+_29") (pintype "bidirectional"))
      (node (ref "R15") (pin "1") (pinfunction "1_1") (pintype "passive"))
    )
    (net (code "66") (name "/RD-") (class "Default")
      (node (ref "IC2") (pin "30") (pinfunction "D-_30") (pintype "bidirectional"))
      (node (ref "R14") (pin "1") (pinfunction "1_1") (pintype "passive"))
    )
    (net (code "67") (name "/RESET") (class "Default")
      (node (ref "C8") (pin "2") (pinfunction "2_2") (pintype "passive"))
      (node (ref "H1") (pin "3") (pinfunction "3_3") (pintype "passive"))
      (node (ref "H5") (pin "5") (pinfunction "5_5") (pintype "passive"))
      (node (ref "H7") (pin "6") (pinfunction "6_6") (pintype "passive"))
      (node (ref "H8") (pin "3") (pinfunction "3_3") (pintype "passive"))
      (node (ref "IC1") (pin "4") (pinfunction "~{RESET}_4") (pintype "bidirectional"))
      (node (ref "R1") (pin "1") (pinfunction "1_1") (pintype "passive"))
      (node (ref "SJ36") (pin "2") (pinfunction "2_2") (pintype "passive"))
      (node (ref "SW1") (pin "1") (pinfunction "1_1") (pintype "passive"))
    )
    (net (code "68") (name "/RESET2") (class "Default")
      (node (ref "H6") (pin "5") (pinfunction "5_5") (pintype "passive"))
      (node (ref "IC2") (pin "24") (pinfunction "RESET_24") (pintype "input"))
      (node (ref "R11") (pin "1") (pinfunction "1_1") (pintype "passive"))
      (node (ref "SW2") (pin "1") (pinfunction "1_1") (pintype "passive"))
    )
    (net (code "69") (name "/RXLED") (class "Default")
      (node (ref "R2") (pin "1") (pinfunction "1_1") (pintype "passive"))
      (node (ref "SJ13") (pin "2") (pinfunction "2_2") (pintype "passive"))
    )
    (net (code "70") (name "/SCL") (class "Default")
      (node (ref "H3") (pin "10") (pinfunction "10_10") (pintype "passive"))
      (node (ref "IC1") (pin "19") (pinfunction "PC0(SCL/PCINT16)_19") (pintype "bidirectional"))
      (node (ref "JP1") (pin "3") (pinfunction "3_3") (pintype "passive"))
      (node (ref "SJ14") (pin "1") (pinfunction "1_1") (pintype "passive"))
    )
    (net (code "71") (name "/SDA") (class "Default")
      (node (ref "H3") (pin "9") (pinfunction "9_9") (pintype "passive"))
      (node (ref "IC1") (pin "20") (pinfunction "PC1(SDA/PCINT17)_20") (pintype "bidirectional"))
      (node (ref "JP1") (pin "4") (pinfunction "4_4") (pintype "passive"))
      (node (ref "SJ15") (pin "1") (pinfunction "1_1") (pintype "passive"))
    )
    (net (code "72") (name "/TCK") (class "Default")
      (node (ref "H7") (pin "1") (pinfunction "1_1") (pintype "passive"))
      (node (ref "IC1") (pin "21") (pinfunction "PC2(TCK/PCINT18)_21") (pintype "bidirectional"))
    )
    (net (code "73") (name "/TDI") (class "Default")
      (node (ref "H7") (pin "9") (pinfunction "9_9") (pintype "passive"))
      (node (ref "IC1") (pin "24") (pinfunction "PC5(TDI/PCINT21)_24") (pintype "bidirectional"))
    )
    (net (code "74") (name "/TDO") (class "Default")
      (node (ref "H7") (pin "3") (pinfunction "3_3") (pintype "passive"))
      (node (ref "IC1") (pin "23") (pinfunction "PC4(TDO/PCINT20)_23") (pintype "bidirectional"))
    )
    (net (code "75") (name "/TMS") (class "Default")
      (node (ref "H7") (pin "5") (pinfunction "5_5") (pintype "passive"))
      (node (ref "IC1") (pin "22") (pinfunction "PC3(TMS/PCINT19)_22") (pintype "bidirectional"))
    )
    (net (code "76") (name "/TXLED") (class "Default")
      (node (ref "R3") (pin "1") (pinfunction "1_1") (pintype "passive"))
      (node (ref "SJ12") (pin "2") (pinfunction "2_2") (pintype "passive"))
    )
    (net (code "77") (name "/USBRXD") (class "Default")
      (node (ref "H14") (pin "4") (pinfunction "4_4") (pintype "passive"))
      (node (ref "IC2") (pin "9") (pinfunction "(TXD1)PD3_9") (pintype "bidirectional"))
      (node (ref "R5") (pin "2") (pinfunction "2_2") (pintype "passive"))
    )
    (net (code "78") (name "/USBTXD") (class "Default")
      (node (ref "H14") (pin "3") (pinfunction "3_3") (pintype "passive"))
      (node (ref "IC2") (pin "8") (pinfunction "(RXD1)PD2_8") (pintype "bidirectional"))
      (node (ref "R4") (pin "2") (pinfunction "2_2") (pintype "passive"))
    )
    (net (code "79") (name "/USBVCC") (class "Default")
      (node (ref "F1") (pin "2") (pinfunction "2_2") (pintype "passive"))
      (node (ref "H15") (pin "1") (pinfunction "1_1") (pintype "passive"))
      (node (ref "IC2") (pin "31") (pinfunction "UVCC_31") (pintype "power_in"))
    )
    (net (code "80") (name "/VIN") (class "Default")
      (node (ref "C19") (pin "1") (pinfunction "1_1") (pintype "passive"))
      (node (ref "D1") (pin "C") (pinfunction "C_C") (pintype "passive"))
      (node (ref "H1") (pin "8") (pinfunction "8_8") (pintype "passive"))
      (node (ref "H8") (pin "8") (pinfunction "8_8") (pintype "passive"))
      (node (ref "IC3") (pin "2") (pinfunction "IN_2") (pintype "power_in"))
      (node (ref "R22") (pin "1") (pinfunction "1_1") (pintype "passive"))
    )
    (net (code "81") (name "/VREF") (class "Default")
      (node (ref "H7") (pin "4") (pinfunction "4_4") (pintype "passive"))
    )
    (net (code "82") (name "3V3") (class "Default")
      (node (ref "C22") (pin "1") (pinfunction "1_1") (pintype "passive"))
      (node (ref "C7") (pin "2") (pinfunction "2_2") (pintype "passive"))
      (node (ref "H1") (pin "4") (pinfunction "4_4") (pintype "passive"))
      (node (ref "H8") (pin "4") (pinfunction "4_4") (pintype "passive"))
      (node (ref "IC4") (pin "5") (pinfunction "OUT_5") (pintype "passive"))
      (node (ref "P4") (pin "4") (pinfunction "VCC_4") (pintype "bidirectional"))
    )
    (net (code "83") (name "5V") (class "Default")
      (node (ref "C10") (pin "1") (pinfunction "1_1") (pintype "passive"))
      (node (ref "C14") (pin "1") (pinfunction "1_1") (pintype "passive"))
      (node (ref "C24") (pin "1") (pinfunction "1_1") (pintype "passive"))
      (node (ref "C25") (pin "1") (pinfunction "1_1") (pintype "passive"))
      (node (ref "C4") (pin "1") (pinfunction "1_1") (pintype "passive"))
      (node (ref "C5") (pin "+") (pinfunction "+_+") (pintype "passive"))
      (node (ref "H1") (pin "2") (pinfunction "2_2") (pintype "passive"))
      (node (ref "H1") (pin "5") (pinfunction "5_5") (pintype "passive"))
      (node (ref "H15") (pin "2") (pinfunction "2_2") (pintype "passive"))
      (node (ref "H5") (pin "2") (pinfunction "2_2") (pintype "passive"))
      (node (ref "H6") (pin "2") (pinfunction "2_2") (pintype "passive"))
      (node (ref "H8") (pin "2") (pinfunction "2_2") (pintype "passive"))
      (node (ref "H8") (pin "5") (pinfunction "5_5") (pintype "passive"))
      (node (ref "IC1") (pin "17") (pinfunction "VCC_17") (pintype "bidirectional"))
      (node (ref "IC1") (pin "38") (pinfunction "VCC_38") (pintype "bidirectional"))
      (node (ref "IC1") (pin "5") (pinfunction "VCC_5") (pintype "bidirectional"))
      (node (ref "IC2") (pin "32") (pinfunction "AVCC_32") (pintype "power_in"))
      (node (ref "IC2") (pin "4") (pinfunction "VCC_4") (pintype "power_in"))
      (node (ref "IC4") (pin "1") (pinfunction "IN_1") (pintype "input"))
      (node (ref "IC4") (pin "3") (pinfunction "~{EN}_3") (pintype "input"))
      (node (ref "JP1") (pin "2") (pinfunction "2_2") (pintype "passive"))
      (node (ref "L2") (pin "2") (pinfunction "2_2") (pintype "passive"))
      (node (ref "LED1") (pin "A") (pinfunction "A_A") (pintype "passive"))
      (node (ref "LED2") (pin "A") (pinfunction "A_A") (pintype "passive"))
      (node (ref "LED3") (pin "A") (pinfunction "A_A") (pintype "passive"))
      (node (ref "LED4") (pin "A") (pinfunction "A_A") (pintype "passive"))
      (node (ref "R1") (pin "2") (pinfunction "2_2") (pintype "passive"))
      (node (ref "R11") (pin "2") (pinfunction "2_2") (pintype "passive"))
    )
    (net (code "84") (name "GND") (class "Default")
      (node (ref "C1") (pin "2") (pinfunction "2_2") (pintype "passive"))
      (node (ref "C10") (pin "2") (pinfunction "2_2") (pintype "passive"))
      (node (ref "C11") (pin "2") (pinfunction "2_2") (pintype "passive"))
      (node (ref "C12") (pin "1") (pinfunction "1_1") (pintype "passive"))
      (node (ref "C13") (pin "1") (pinfunction "1_1") (pintype "passive"))
      (node (ref "C14") (pin "2") (pinfunction "2_2") (pintype "passive"))
      (node (ref "C16") (pin "2") (pinfunction "2_2") (pintype "passive"))
      (node (ref "C17") (pin "2") (pinfunction "2_2") (pintype "passive"))
      (node (ref "C18") (pin "2") (pinfunction "2_2") (pintype "passive"))
      (node (ref "C19") (pin "2") (pinfunction "2_2") (pintype "passive"))
      (node (ref "C2") (pin "1") (pinfunction "1_1") (pintype "passive"))
      (node (ref "C20") (pin "2") (pinfunction "2_2") (pintype "passive"))
      (node (ref "C21") (pin "2") (pinfunction "2_2") (pintype "passive"))
      (node (ref "C22") (pin "2") (pinfunction "2_2") (pintype "passive"))
      (node (ref "C23") (pin "2") (pinfunction "2_2") (pintype "passive"))
      (node (ref "C24") (pin "2") (pinfunction "2_2") (pintype "passive"))
      (node (ref "C25") (pin "2") (pinfunction "2_2") (pintype "passive"))
      (node (ref "C3") (pin "1") (pinfunction "1_1") (pintype "passive"))
      (node (ref "C4") (pin "2") (pinfunction "2_2") (pintype "passive"))
      (node (ref "C5") (pin "-") (pinfunction "-_-") (pintype "passive"))
      (node (ref "C6") (pin "2") (pinfunction "2_2") (pintype "passive"))
      (node (ref "C7") (pin "1") (pinfunction "1_1") (pintype "passive"))
      (node (ref "C9") (pin "2") (pinfunction "2_2") (pintype "passive"))
      (node (ref "H1") (pin "6") (pinfunction "6_6") (pintype "passive"))
      (node (ref "H1") (pin "7") (pinfunction "7_7") (pintype "passive"))
      (node (ref "H3") (pin "7") (pinfunction "7_7") (pintype "passive"))
      (node (ref "H5") (pin "6") (pinfunction "6_6") (pintype "passive"))
      (node (ref "H6") (pin "6") (pinfunction "6_6") (pintype "passive"))
      (node (ref "H7") (pin "10") (pinfunction "10_10") (pintype "passive"))
      (node (ref "H7") (pin "2") (pinfunction "2_2") (pintype "passive"))
      (node (ref "H8") (pin "6") (pinfunction "6_6") (pintype "passive"))
      (node (ref "H8") (pin "7") (pinfunction "7_7") (pintype "passive"))
      (node (ref "IC1") (pin "18") (pinfunction "GND_18") (pintype "bidirectional"))
      (node (ref "IC1") (pin "28") (pinfunction "GND_28") (pintype "bidirectional"))
      (node (ref "IC1") (pin "39") (pinfunction "GND_39") (pintype "bidirectional"))
      (node (ref "IC1") (pin "6") (pinfunction "GND_6") (pintype "bidirectional"))
      (node (ref "IC1") (pin "TGND") (pinfunction "TGND_TGND") (pintype "bidirectional"))
      (node (ref "IC2") (pin "3") (pinfunction "GND_3") (pintype "power_in"))
      (node (ref "IC2") (pin "EXP") (pinfunction "PAD_EXP") (pintype "power_in"))
      (node (ref "IC3") (pin "4") (pinfunction "GND_4") (pintype "power_in"))
      (node (ref "IC3") (pin "9") (pinfunction "TGND_9") (pintype "power_in"))
      (node (ref "IC4") (pin "2") (pinfunction "GND_2") (pintype "power_in"))
      (node (ref "J1") (pin "GND") (pinfunction "GND_GND") (pintype "bidirectional"))
      (node (ref "J1") (pin "GNDBREAK") (pinfunction "GNDBREAK_GNDBREAK") (pintype "bidirectional"))
      (node (ref "JP1") (pin "1") (pinfunction "1_1") (pintype "passive"))
      (node (ref "P4") (pin "6") (pinfunction "GND_6") (pintype "bidirectional"))
      (node (ref "P4") (pin "CD2") (pinfunction "CD2_CD2") (pintype "bidirectional"))
      (node (ref "P4") (pin "GND1") (pinfunction "SHIELD1_GND1") (pintype "bidirectional"))
      (node (ref "P4") (pin "GND2") (pinfunction "SHIELD2_GND2") (pintype "bidirectional"))
      (node (ref "Q1") (pin "2") (pinfunction "S_2") (pintype "passive"))
      (node (ref "R10") (pin "1") (pinfunction "1_1") (pintype "passive"))
      (node (ref "R19") (pin "1") (pinfunction "1_1") (pintype "passive"))
      (node (ref "R20") (pin "1") (pinfunction "1_1") (pintype "passive"))
      (node (ref "R21") (pin "1") (pinfunction "1_1") (pintype "passive"))
      (node (ref "R25") (pin "1") (pinfunction "1_1") (pintype "passive"))
      (node (ref "SJ2") (pin "2") (pinfunction "2_2") (pintype "passive"))
      (node (ref "SJ3") (pin "1") (pinfunction "1_1") (pintype "passive"))
      (node (ref "SW1") (pin "2") (pinfunction "2_2") (pintype "passive"))
      (node (ref "SW1") (pin "3") (pinfunction "3_3") (pintype "passive"))
      (node (ref "SW2") (pin "2") (pinfunction "2_2") (pintype "passive"))
      (node (ref "SW2") (pin "3") (pinfunction "3_3") (pintype "passive"))
    )
    (net (code "85") (name "Net-(C8-Pad1)") (class "Default")
      (node (ref "C8") (pin "1") (pinfunction "1_1") (pintype "passive"))
      (node (ref "SJ1") (pin "2") (pinfunction "2_2") (pintype "passive"))
    )
    (net (code "86") (name "Net-(C13-Pad2)") (class "Default")
      (node (ref "C13") (pin "2") (pinfunction "2_2") (pintype "passive"))
      (node (ref "R12") (pin "1") (pinfunction "1_1") (pintype "passive"))
      (node (ref "R13") (pin "2") (pinfunction "2_2") (pintype "passive"))
      (node (ref "XTL2") (pin "1") (pinfunction "1_1") (pintype "passive"))
    )
    (net (code "87") (name "Net-(C17-Pad1)") (class "Default")
      (node (ref "C17") (pin "1") (pinfunction "1_1") (pintype "passive"))
      (node (ref "R24") (pin "1") (pinfunction "1_1") (pintype "passive"))
    )
    (net (code "88") (name "Net-(D1-PadA)") (class "Default")
      (node (ref "D1") (pin "A") (pinfunction "A_A") (pintype "passive"))
      (node (ref "J1") (pin "PWR") (pinfunction "PWR_PWR") (pintype "bidirectional"))
    )
    (net (code "89") (name "Net-(F1-Pad1)") (class "Default")
      (node (ref "F1") (pin "1") (pinfunction "1_1") (pintype "passive"))
      (node (ref "P1") (pin "VBUS") (pinfunction "VBUS_VBUS") (pintype "bidirectional"))
    )
    (net (code "90") (name "Net-(H17-Pad1)") (class "Default")
      (node (ref "H17") (pin "1") (pinfunction "1_1") (pintype "passive"))
      (node (ref "P4") (pin "CD1") (pinfunction "CD1_CD1") (pintype "bidirectional"))
    )
    (net (code "91") (name "Net-(IC1-PC6(TOSC1{slash}PCINT22))") (class "Default")
      (node (ref "C1") (pin "1") (pinfunction "1_1") (pintype "passive"))
      (node (ref "IC1") (pin "25") (pinfunction "PC6(TOSC1/PCINT22)_25") (pintype "bidirectional"))
      (node (ref "XTL3") (pin "2") (pinfunction "2_2") (pintype "passive"))
    )
    (net (code "92") (name "Net-(IC1-PC7(TOSC2{slash}PCINT23))") (class "Default")
      (node (ref "C11") (pin "1") (pinfunction "1_1") (pintype "passive"))
      (node (ref "IC1") (pin "26") (pinfunction "PC7(TOSC2/PCINT23)_26") (pintype "bidirectional"))
      (node (ref "XTL3") (pin "1") (pinfunction "1_1") (pintype "passive"))
    )
    (net (code "93") (name "Net-(IC1-XTAL1)") (class "Default")
      (node (ref "C3") (pin "2") (pinfunction "2_2") (pintype "passive"))
      (node (ref "IC1") (pin "8") (pinfunction "XTAL1_8") (pintype "bidirectional"))
      (node (ref "R6") (pin "1") (pinfunction "1_1") (pintype "passive"))
      (node (ref "XTL1") (pin "1") (pinfunction "1_1") (pintype "passive"))
    )
    (net (code "94") (name "Net-(IC1-XTAL2)") (class "Default")
      (node (ref "C2") (pin "2") (pinfunction "2_2") (pintype "passive"))
      (node (ref "IC1") (pin "7") (pinfunction "XTAL2_7") (pintype "bidirectional"))
      (node (ref "R6") (pin "2") (pinfunction "2_2") (pintype "passive"))
      (node (ref "XTL1") (pin "2") (pinfunction "2_2") (pintype "passive"))
    )
    (net (code "95") (name "Net-(IC2-UCAP)") (class "Default")
      (node (ref "C6") (pin "1") (pinfunction "1_1") (pintype "passive"))
      (node (ref "IC2") (pin "27") (pinfunction "UCAP_27") (pintype "passive"))
    )
    (net (code "96") (name "Net-(IC2-UGND)") (class "Default")
      (node (ref "IC2") (pin "28") (pinfunction "UGND_28") (pintype "power_in"))
      (node (ref "L1") (pin "2") (pinfunction "2_2") (pintype "passive"))
      (node (ref "P1") (pin "GND") (pinfunction "GND_GND") (pintype "bidirectional"))
      (node (ref "SJ2") (pin "1") (pinfunction "1_1") (pintype "passive"))
    )
    (net (code "97") (name "Net-(IC2-XTAL1)") (class "Default")
      (node (ref "IC2") (pin "1") (pinfunction "XTAL1_1") (pintype "bidirectional"))
      (node (ref "R13") (pin "1") (pinfunction "1_1") (pintype "passive"))
    )
    (net (code "98") (name "Net-(IC2-XTAL2)") (class "Default")
      (node (ref "C12") (pin "2") (pinfunction "2_2") (pintype "passive"))
      (node (ref "IC2") (pin "2") (pinfunction "XTAL2_2") (pintype "bidirectional"))
      (node (ref "R12") (pin "2") (pinfunction "2_2") (pintype "passive"))
      (node (ref "XTL2") (pin "2") (pinfunction "2_2") (pintype "passive"))
    )
    (net (code "99") (name "Net-(IC3-BS)") (class "Default")
      (node (ref "C15") (pin "2") (pinfunction "2_2") (pintype "passive"))
      (node (ref "IC3") (pin "1") (pinfunction "BS_1") (pintype "bidirectional"))
    )
    (net (code "100") (name "Net-(IC3-COMP)") (class "Default")
      (node (ref "C16") (pin "1") (pinfunction "1_1") (pintype "passive"))
      (node (ref "IC3") (pin "6") (pinfunction "COMP_6") (pintype "bidirectional"))
      (node (ref "R24") (pin "2") (pinfunction "2_2") (pintype "passive"))
    )
    (net (code "101") (name "Net-(IC3-EN)") (class "Default")
      (node (ref "IC3") (pin "7") (pinfunction "EN_7") (pintype "input"))
      (node (ref "R22") (pin "2") (pinfunction "2_2") (pintype "passive"))
    )
    (net (code "102") (name "Net-(IC3-FB)") (class "Default")
      (node (ref "IC3") (pin "5") (pinfunction "FB_5") (pintype "bidirectional"))
      (node (ref "R23") (pin "1") (pinfunction "1_1") (pintype "passive"))
      (node (ref "R25") (pin "2") (pinfunction "2_2") (pintype "passive"))
    )
    (net (code "103") (name "Net-(IC3-SS)") (class "Default")
      (node (ref "C18") (pin "1") (pinfunction "1_1") (pintype "passive"))
      (node (ref "IC3") (pin "8") (pinfunction "SS_8") (pintype "bidirectional"))
    )
    (net (code "104") (name "Net-(IC3-SW)") (class "Default")
      (node (ref "C15") (pin "1") (pinfunction "1_1") (pintype "passive"))
      (node (ref "IC3") (pin "3") (pinfunction "SW_3") (pintype "bidirectional"))
      (node (ref "L3") (pin "1") (pinfunction "1_1") (pintype "bidirectional"))
    )
    (net (code "105") (name "Net-(L1-Pad1)") (class "Default")
      (node (ref "L1") (pin "1") (pinfunction "1_1") (pintype "passive"))
      (node (ref "P1") (pin "FIX1") (pinfunction "FIX1_FIX1") (pintype "bidirectional"))
      (node (ref "P1") (pin "FIX2") (pinfunction "FIX2_FIX2") (pintype "bidirectional"))
      (node (ref "P1") (pin "PIN1") (pinfunction "PIN1_PIN1") (pintype "bidirectional"))
      (node (ref "P1") (pin "PIN2") (pinfunction "PIN2_PIN2") (pintype "bidirectional"))
      (node (ref "P1") (pin "TAB1") (pinfunction "TAB1_TAB1") (pintype "bidirectional"))
      (node (ref "P1") (pin "TAB2") (pinfunction "TAB2_TAB2") (pintype "bidirectional"))
      (node (ref "Z1") (pin "2") (pinfunction "2_2") (pintype "passive"))
      (node (ref "Z2") (pin "2") (pinfunction "2_2") (pintype "passive"))
    )
    (net (code "106") (name "Net-(LED1-PadC)") (class "Default")
      (node (ref "LED1") (pin "C") (pinfunction "C_C") (pintype "passive"))
      (node (ref "R2") (pin "2") (pinfunction "2_2") (pintype "passive"))
    )
    (net (code "107") (name "Net-(LED2-PadC)") (class "Default")
      (node (ref "LED2") (pin "C") (pinfunction "C_C") (pintype "passive"))
      (node (ref "R3") (pin "2") (pinfunction "2_2") (pintype "passive"))
    )
    (net (code "108") (name "Net-(LED3-PadC)") (class "Default")
      (node (ref "LED3") (pin "C") (pinfunction "C_C") (pintype "passive"))
      (node (ref "R7") (pin "2") (pinfunction "2_2") (pintype "passive"))
    )
    (net (code "109") (name "Net-(LED4-PadC)") (class "Default")
      (node (ref "LED4") (pin "C") (pinfunction "C_C") (pintype "passive"))
      (node (ref "R10") (pin "2") (pinfunction "2_2") (pintype "passive"))
    )
    (net (code "110") (name "Net-(P1-PadD+)") (class "Default")
      (node (ref "P1") (pin "D+") (pinfunction "D+_D+") (pintype "bidirectional"))
      (node (ref "R15") (pin "2") (pinfunction "2_2") (pintype "passive"))
      (node (ref "Z1") (pin "1") (pinfunction "1_1") (pintype "passive"))
    )
    (net (code "111") (name "Net-(P1-PadD-)") (class "Default")
      (node (ref "P1") (pin "D-") (pinfunction "D-_D-") (pintype "bidirectional"))
      (node (ref "R14") (pin "2") (pinfunction "2_2") (pintype "passive"))
      (node (ref "Z2") (pin "1") (pinfunction "1_1") (pintype "passive"))
    )
    (net (code "112") (name "Net-(P4-CS)") (class "Default")
      (node (ref "P4") (pin "2") (pinfunction "CS_2") (pintype "bidirectional"))
      (node (ref "R16") (pin "1") (pinfunction "1_1") (pintype "passive"))
      (node (ref "R21") (pin "2") (pinfunction "2_2") (pintype "passive"))
    )
    (net (code "113") (name "Net-(P4-DI)") (class "Default")
      (node (ref "P4") (pin "3") (pinfunction "DI_3") (pintype "bidirectional"))
      (node (ref "R17") (pin "1") (pinfunction "1_1") (pintype "passive"))
      (node (ref "R20") (pin "2") (pinfunction "2_2") (pintype "passive"))
    )
    (net (code "114") (name "Net-(P4-SCK)") (class "Default")
      (node (ref "P4") (pin "5") (pinfunction "SCK_5") (pintype "bidirectional"))
      (node (ref "R18") (pin "1") (pinfunction "1_1") (pintype "passive"))
      (node (ref "R19") (pin "2") (pinfunction "2_2") (pintype "passive"))
    )
    (net (code "115") (name "Net-(Q1-D)") (class "Default")
      (node (ref "Q1") (pin "3") (pinfunction "D_3") (pintype "passive"))
      (node (ref "R7") (pin "1") (pinfunction "1_1") (pintype "passive"))
    )
    (net (code "116") (name "Net-(R8-Pad1)") (class "Default")
      (node (ref "R8") (pin "1") (pinfunction "1_1") (pintype "passive"))
      (node (ref "SJ30") (pin "2") (pinfunction "2_2") (pintype "passive"))
    )
    (net (code "117") (name "Net-(R9-Pad1)") (class "Default")
      (node (ref "R9") (pin "1") (pinfunction "1_1") (pintype "passive"))
      (node (ref "SJ31") (pin "2") (pinfunction "2_2") (pintype "passive"))
    )
    (net (code "118") (name "Net-(R26-Pad1)") (class "Default")
      (node (ref "R26") (pin "1") (pinfunction "1_1") (pintype "passive"))
      (node (ref "SJ32") (pin "2") (pinfunction "2_2") (pintype "passive"))
    )
    (net (code "119") (name "unconnected-(H7-Pad7)") (class "Default")
      (node (ref "H7") (pin "7") (pinfunction "7_7") (pintype "passive"))
    )
    (net (code "120") (name "unconnected-(H7-Pad8)") (class "Default")
      (node (ref "H7") (pin "8") (pinfunction "8_8") (pintype "passive"))
    )
    (net (code "121") (name "unconnected-(IC2-PC2-Pad5)") (class "Default")
      (node (ref "IC2") (pin "5") (pinfunction "PC2_5") (pintype "bidirectional"))
    )
    (net (code "122") (name "unconnected-(IC2-PC4-Pad26)") (class "Default")
      (node (ref "IC2") (pin "26") (pinfunction "PC4_26") (pintype "bidirectional"))
    )
    (net (code "123") (name "unconnected-(IC2-PC5-Pad25)") (class "Default")
      (node (ref "IC2") (pin "25") (pinfunction "PC5_25") (pintype "bidirectional"))
    )
    (net (code "124") (name "unconnected-(IC2-PC6-Pad23)") (class "Default")
      (node (ref "IC2") (pin "23") (pinfunction "PC6_23") (pintype "bidirectional"))
    )
    (net (code "125") (name "unconnected-(IC2-PC7-Pad22)") (class "Default")
      (node (ref "IC2") (pin "22") (pinfunction "PC7_22") (pintype "bidirectional"))
    )
    (net (code "126") (name "unconnected-(IC4-NC{slash}FB-Pad4)") (class "Default")
      (node (ref "IC4") (pin "4") (pinfunction "NC/FB_4") (pintype "passive"))
    )
    (net (code "127") (name "unconnected-(P1-PadID)") (class "Default")
      (node (ref "P1") (pin "ID") (pinfunction "ID_ID") (pintype "bidirectional"))
    )
    (net (code "128") (name "unconnected-(P4-NC-Pad1)") (class "Default")
      (node (ref "P4") (pin "1") (pinfunction "NC_1") (pintype "bidirectional"))
    )
    (net (code "129") (name "unconnected-(P4-RSV-Pad8)") (class "Default")
      (node (ref "P4") (pin "8") (pinfunction "RSV_8") (pintype "bidirectional"))
    )
  )
)
